# GPSsd1_1.net
KiCad netlist of a schematic drawn in EAGLE
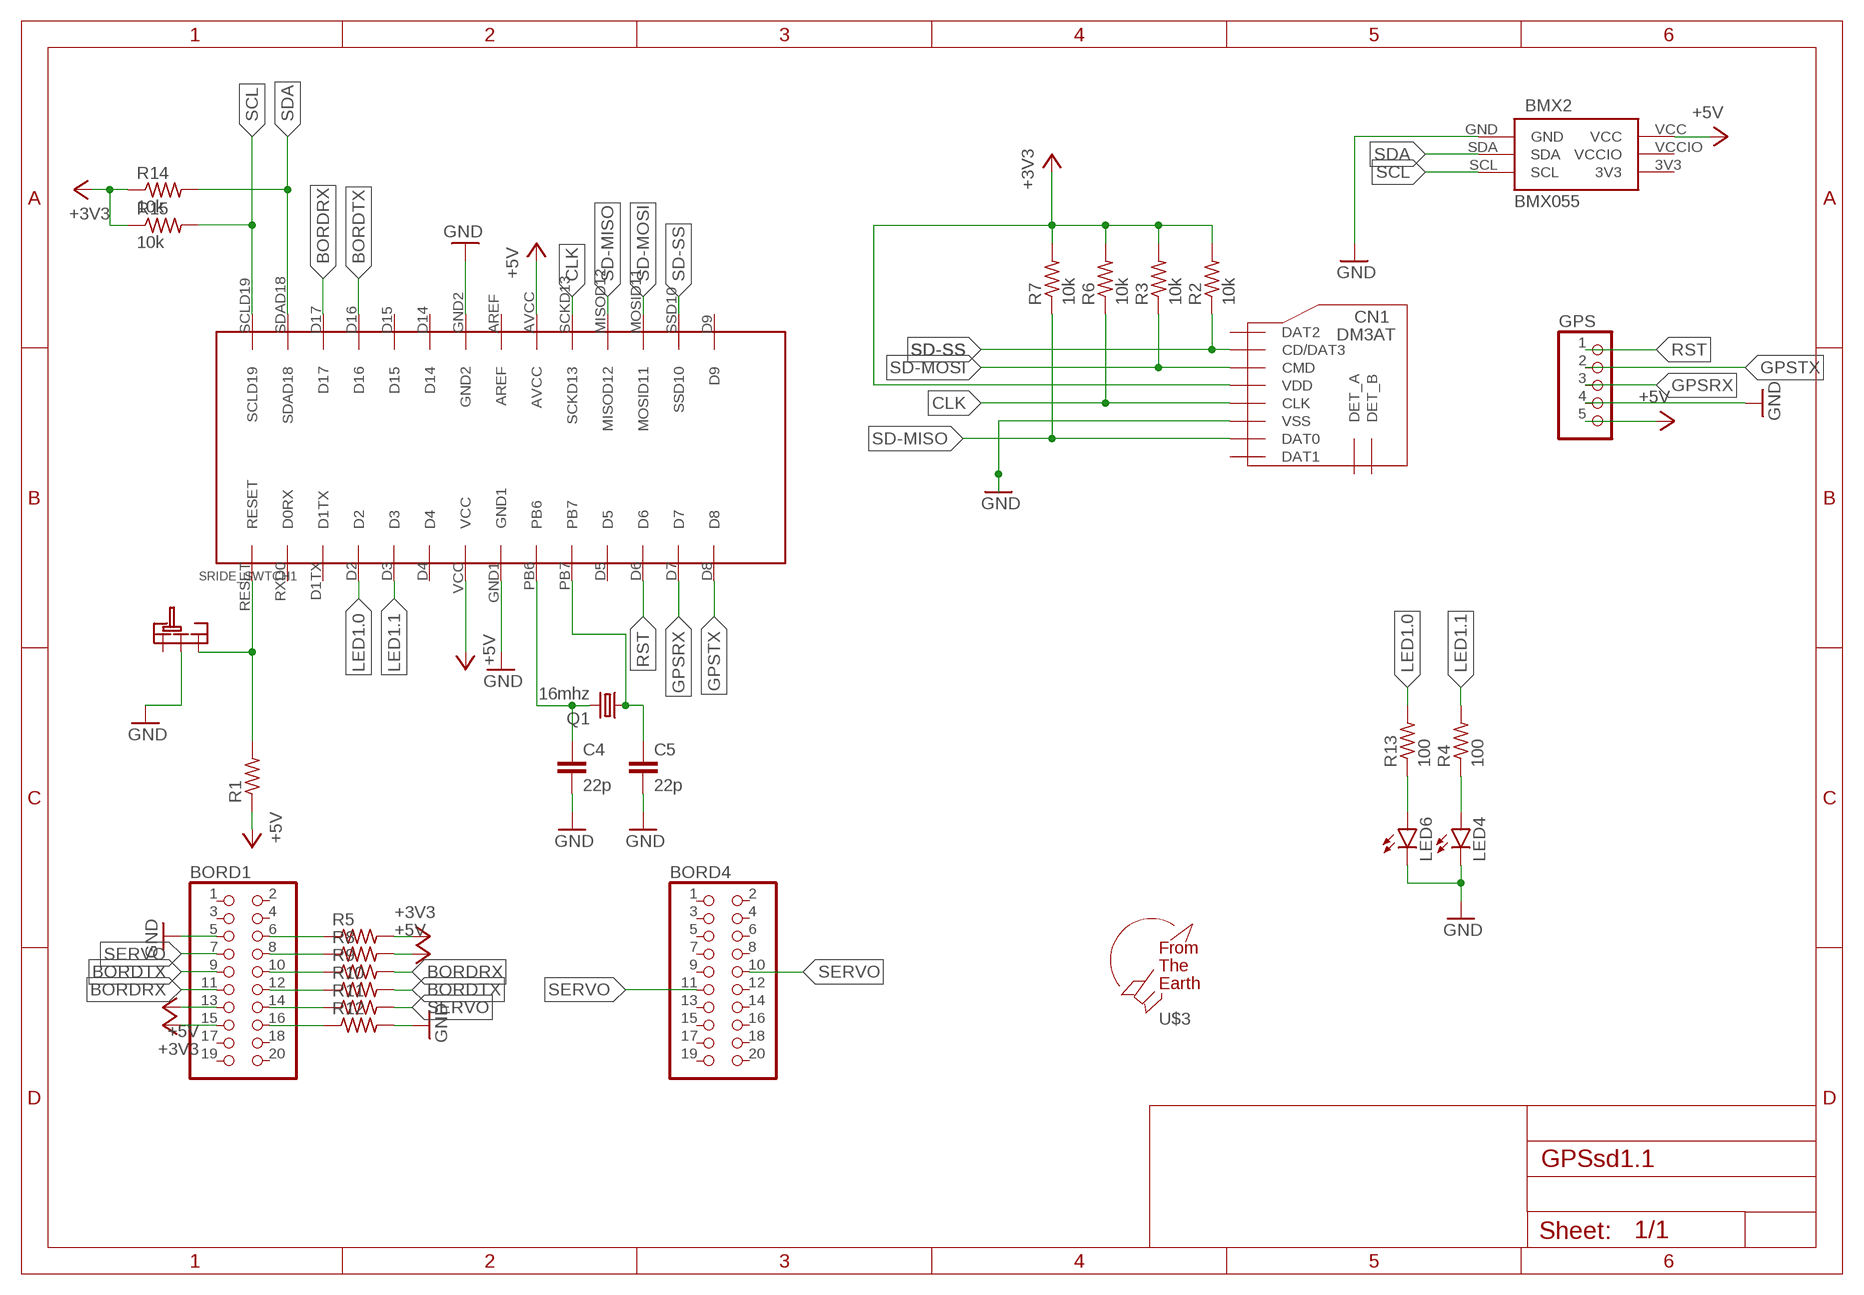
[diagram p0: schematic, sheet 1]

(export (version "E")
  (design (tool "Eeschema 10.0.6"))
  (components
    (comp (ref "BMX2")
      (value "BMX055")
      (footprint "eagle-import:BMX055")
      (libsource (lib "eagle-import") (part "BMX055"))
    )
    (comp (ref "BORD1")
      (value "PINHD-2X10/90")
      (footprint "eagle-import:2X10_90")
      (libsource (lib "eagle-import") (part "PINHD-2X10/90"))
    )
    (comp (ref "BORD4")
      (value "PINHD-2X10/90")
      (footprint "eagle-import:2X10_90")
      (libsource (lib "eagle-import") (part "PINHD-2X10/90"))
    )
    (comp (ref "C4")
      (value "22p")
      (footprint "eagle-import:C025-024X044")
      (libsource (lib "eagle-import") (part "C-EU025-024X044"))
    )
    (comp (ref "C5")
      (value "22p")
      (footprint "eagle-import:C025-024X044")
      (libsource (lib "eagle-import") (part "C-EU025-024X044"))
    )
    (comp (ref "CN1")
      (value "DM3AT")
      (footprint "eagle-import:DM3AT")
      (libsource (lib "eagle-import") (part "DM3AT"))
    )
    (comp (ref "GPS")
      (value "PINHD-1X55X2MM")
      (footprint "eagle-import:1_05X2MM")
      (libsource (lib "eagle-import") (part "PINHD-1X55X2MM"))
    )
    (comp (ref "LED4")
      (value "LED5MM")
      (footprint "eagle-import:LED5MM")
      (libsource (lib "eagle-import") (part "LED5MM"))
    )
    (comp (ref "LED6")
      (value "LED5MM")
      (footprint "eagle-import:LED5MM")
      (libsource (lib "eagle-import") (part "LED5MM"))
    )
    (comp (ref "Q1")
      (value "16mhz")
      (footprint "eagle-import:HC49_S")
      (libsource (lib "eagle-import") (part "CRYSTALHC49S"))
    )
    (comp (ref "R1")
      (value "R-US_0204/7")
      (footprint "eagle-import:0204_7")
      (libsource (lib "eagle-import") (part "R-US_0204/7"))
    )
    (comp (ref "R2")
      (value "10k")
      (footprint "eagle-import:0204_7")
      (libsource (lib "eagle-import") (part "R-US_0204/7"))
    )
    (comp (ref "R3")
      (value "10k")
      (footprint "eagle-import:0204_7")
      (libsource (lib "eagle-import") (part "R-US_0204/7"))
    )
    (comp (ref "R4")
      (value "100")
      (footprint "eagle-import:0204_7")
      (libsource (lib "eagle-import") (part "R-US_0204/7"))
    )
    (comp (ref "R5")
      (value "R-US_0204/7")
      (footprint "eagle-import:0204_7")
      (libsource (lib "eagle-import") (part "R-US_0204/7"))
    )
    (comp (ref "R6")
      (value "10k")
      (footprint "eagle-import:0204_7")
      (libsource (lib "eagle-import") (part "R-US_0204/7"))
    )
    (comp (ref "R7")
      (value "10k")
      (footprint "eagle-import:0204_7")
      (libsource (lib "eagle-import") (part "R-US_0204/7"))
    )
    (comp (ref "R8")
      (value "R-US_0204/7")
      (footprint "eagle-import:0204_7")
      (libsource (lib "eagle-import") (part "R-US_0204/7"))
    )
    (comp (ref "R9")
      (value "R-US_0204/7")
      (footprint "eagle-import:0204_7")
      (libsource (lib "eagle-import") (part "R-US_0204/7"))
    )
    (comp (ref "R10")
      (value "R-US_0204/7")
      (footprint "eagle-import:0204_7")
      (libsource (lib "eagle-import") (part "R-US_0204/7"))
    )
    (comp (ref "R11")
      (value "R-US_0204/7")
      (footprint "eagle-import:0204_7")
      (libsource (lib "eagle-import") (part "R-US_0204/7"))
    )
    (comp (ref "R12")
      (value "R-US_0204/7")
      (footprint "eagle-import:0204_7")
      (libsource (lib "eagle-import") (part "R-US_0204/7"))
    )
    (comp (ref "R13")
      (value "100")
      (footprint "eagle-import:0204_7")
      (libsource (lib "eagle-import") (part "R-US_0204/7"))
    )
    (comp (ref "R14")
      (value "10k")
      (footprint "eagle-import:0204_7")
      (libsource (lib "eagle-import") (part "R-US_0204/7"))
    )
    (comp (ref "R15")
      (value "10k")
      (footprint "eagle-import:0204_7")
      (libsource (lib "eagle-import") (part "R-US_0204/7"))
    )
    (comp (ref "SRIDE_SWTCH1")
      (value "SRIDE_SWITCH")
      (footprint "eagle-import:SRIDE_SWITCH")
      (libsource (lib "eagle-import") (part "SRIDE_SWITCH"))
    )
    (comp (ref "U$1")
      (value "ATMEGA238P")
      (footprint "eagle-import:ATMEGA328P")
      (libsource (lib "eagle-import") (part "ATMEGA238P"))
    )
    (comp (ref "U$3")
      (value "F.T.E.LOGO")
      (footprint "eagle-import:LOGO")
      (libsource (lib "eagle-import") (part "F.T.E.LOGO"))
    )
  )
  (nets
    (net (code "1") (name "+3V3") (class "Default")
      (node (ref "BORD1") (pin "15") (pinfunction "15_15") (pintype "passive"))
      (node (ref "CN1") (pin "VDD") (pinfunction "VDD_VDD") (pintype "bidirectional"))
      (node (ref "R14") (pin "1") (pinfunction "1_1") (pintype "passive"))
      (node (ref "R15") (pin "1") (pinfunction "1_1") (pintype "passive"))
      (node (ref "R2") (pin "2") (pinfunction "2_2") (pintype "passive"))
      (node (ref "R3") (pin "2") (pinfunction "2_2") (pintype "passive"))
      (node (ref "R5") (pin "2") (pinfunction "2_2") (pintype "passive"))
      (node (ref "R6") (pin "2") (pinfunction "2_2") (pintype "passive"))
      (node (ref "R7") (pin "2") (pinfunction "2_2") (pintype "passive"))
    )
    (net (code "2") (name "+5V") (class "Default")
      (node (ref "BMX2") (pin "VCC") (pinfunction "VCC_VCC") (pintype "power_in"))
      (node (ref "BORD1") (pin "13") (pinfunction "13_13") (pintype "passive"))
      (node (ref "GPS") (pin "5") (pinfunction "5_5") (pintype "passive"))
      (node (ref "R1") (pin "1") (pinfunction "1_1") (pintype "passive"))
      (node (ref "R8") (pin "2") (pinfunction "2_2") (pintype "passive"))
      (node (ref "U$1") (pin "AVCC") (pinfunction "AVCC_AVCC") (pintype "bidirectional"))
      (node (ref "U$1") (pin "VCC") (pinfunction "VCC_VCC") (pintype "bidirectional"))
    )
    (net (code "3") (name "/3V3") (class "Default")
      (node (ref "BMX2") (pin "3V3") (pinfunction "3V3_3V3") (pintype "power_in"))
    )
    (net (code "4") (name "/VCCIO") (class "Default")
      (node (ref "BMX2") (pin "VCCIO") (pinfunction "VCCIO_VCCIO") (pintype "power_in"))
    )
    (net (code "5") (name "BORDRX") (class "Default")
      (node (ref "BORD1") (pin "11") (pinfunction "11_11") (pintype "passive"))
      (node (ref "R9") (pin "2") (pinfunction "2_2") (pintype "passive"))
      (node (ref "U$1") (pin "D17") (pinfunction "D17_D17") (pintype "bidirectional"))
    )
    (net (code "6") (name "BORDTX") (class "Default")
      (node (ref "BORD1") (pin "9") (pinfunction "9_9") (pintype "passive"))
      (node (ref "R10") (pin "2") (pinfunction "2_2") (pintype "passive"))
      (node (ref "U$1") (pin "D16") (pinfunction "D16_D16") (pintype "bidirectional"))
    )
    (net (code "7") (name "CLK") (class "Default")
      (node (ref "CN1") (pin "CLK") (pinfunction "CLK_CLK") (pintype "bidirectional"))
      (node (ref "R6") (pin "1") (pinfunction "1_1") (pintype "passive"))
      (node (ref "U$1") (pin "SCKD13") (pinfunction "SCKD13_SCKD13") (pintype "bidirectional"))
    )
    (net (code "8") (name "GND") (class "Default")
      (node (ref "BMX2") (pin "GND") (pinfunction "GND_GND") (pintype "power_in"))
      (node (ref "BORD1") (pin "5") (pinfunction "5_5") (pintype "passive"))
      (node (ref "C4") (pin "2") (pinfunction "2_2") (pintype "passive"))
      (node (ref "C5") (pin "2") (pinfunction "2_2") (pintype "passive"))
      (node (ref "CN1") (pin "VSS") (pinfunction "VSS_VSS") (pintype "bidirectional"))
      (node (ref "GPS") (pin "4") (pinfunction "4_4") (pintype "passive"))
      (node (ref "LED4") (pin "K") (pinfunction "C_K") (pintype "passive"))
      (node (ref "LED6") (pin "K") (pinfunction "C_K") (pintype "passive"))
      (node (ref "R12") (pin "2") (pinfunction "2_2") (pintype "passive"))
      (node (ref "SRIDE_SWTCH1") (pin "LR") (pinfunction "LR_LR") (pintype "bidirectional"))
      (node (ref "U$1") (pin "GND1") (pinfunction "GND1_GND1") (pintype "bidirectional"))
      (node (ref "U$1") (pin "GND2") (pinfunction "GND2_GND2") (pintype "bidirectional"))
    )
    (net (code "9") (name "GPSRX") (class "Default")
      (node (ref "GPS") (pin "3") (pinfunction "3_3") (pintype "passive"))
      (node (ref "U$1") (pin "D7") (pinfunction "D7_D7") (pintype "bidirectional"))
    )
    (net (code "10") (name "GPSTX") (class "Default")
      (node (ref "GPS") (pin "2") (pinfunction "2_2") (pintype "passive"))
      (node (ref "U$1") (pin "D8") (pinfunction "D8_D8") (pintype "bidirectional"))
    )
    (net (code "11") (name "LED1.0") (class "Default")
      (node (ref "R13") (pin "2") (pinfunction "2_2") (pintype "passive"))
      (node (ref "U$1") (pin "D2") (pinfunction "D2_D2") (pintype "bidirectional"))
    )
    (net (code "12") (name "LED1.1") (class "Default")
      (node (ref "R4") (pin "2") (pinfunction "2_2") (pintype "passive"))
      (node (ref "U$1") (pin "D3") (pinfunction "D3_D3") (pintype "bidirectional"))
    )
    (net (code "13") (name "Net-(BORD1-Pad6)") (class "Default")
      (node (ref "BORD1") (pin "6") (pinfunction "6_6") (pintype "passive"))
      (node (ref "R5") (pin "1") (pinfunction "1_1") (pintype "passive"))
    )
    (net (code "14") (name "Net-(BORD1-Pad8)") (class "Default")
      (node (ref "BORD1") (pin "8") (pinfunction "8_8") (pintype "passive"))
      (node (ref "R8") (pin "1") (pinfunction "1_1") (pintype "passive"))
    )
    (net (code "15") (name "Net-(BORD1-Pad10)") (class "Default")
      (node (ref "BORD1") (pin "10") (pinfunction "10_10") (pintype "passive"))
      (node (ref "R9") (pin "1") (pinfunction "1_1") (pintype "passive"))
    )
    (net (code "16") (name "Net-(BORD1-Pad12)") (class "Default")
      (node (ref "BORD1") (pin "12") (pinfunction "12_12") (pintype "passive"))
      (node (ref "R10") (pin "1") (pinfunction "1_1") (pintype "passive"))
    )
    (net (code "17") (name "Net-(BORD1-Pad14)") (class "Default")
      (node (ref "BORD1") (pin "14") (pinfunction "14_14") (pintype "passive"))
      (node (ref "R11") (pin "1") (pinfunction "1_1") (pintype "passive"))
    )
    (net (code "18") (name "Net-(BORD1-Pad16)") (class "Default")
      (node (ref "BORD1") (pin "16") (pinfunction "16_16") (pintype "passive"))
      (node (ref "R12") (pin "1") (pinfunction "1_1") (pintype "passive"))
    )
    (net (code "19") (name "Net-(C4-Pad1)") (class "Default")
      (node (ref "C4") (pin "1") (pinfunction "1_1") (pintype "passive"))
      (node (ref "Q1") (pin "2") (pinfunction "2_2") (pintype "passive"))
      (node (ref "U$1") (pin "PB6") (pinfunction "PB6_PB6") (pintype "bidirectional"))
    )
    (net (code "20") (name "Net-(C5-Pad1)") (class "Default")
      (node (ref "C5") (pin "1") (pinfunction "1_1") (pintype "passive"))
      (node (ref "Q1") (pin "1") (pinfunction "1_1") (pintype "passive"))
      (node (ref "U$1") (pin "PB7") (pinfunction "PB7_PB7") (pintype "bidirectional"))
    )
    (net (code "21") (name "Net-(LED4-PadA)") (class "Default")
      (node (ref "LED4") (pin "A") (pinfunction "A_A") (pintype "passive"))
      (node (ref "R4") (pin "1") (pinfunction "1_1") (pintype "passive"))
    )
    (net (code "22") (name "Net-(LED6-PadA)") (class "Default")
      (node (ref "LED6") (pin "A") (pinfunction "A_A") (pintype "passive"))
      (node (ref "R13") (pin "1") (pinfunction "1_1") (pintype "passive"))
    )
    (net (code "23") (name "Net-(R1-Pad2)") (class "Default")
      (node (ref "R1") (pin "2") (pinfunction "2_2") (pintype "passive"))
      (node (ref "SRIDE_SWTCH1") (pin "R") (pinfunction "R_R") (pintype "bidirectional"))
      (node (ref "U$1") (pin "RESET") (pinfunction "RESET_RESET") (pintype "bidirectional"))
    )
    (net (code "24") (name "RST") (class "Default")
      (node (ref "GPS") (pin "1") (pinfunction "1_1") (pintype "passive"))
      (node (ref "U$1") (pin "D6") (pinfunction "D6_D6") (pintype "bidirectional"))
    )
    (net (code "25") (name "SCL") (class "Default")
      (node (ref "BMX2") (pin "SCL") (pinfunction "SCL_SCL") (pintype "bidirectional"))
      (node (ref "R15") (pin "2") (pinfunction "2_2") (pintype "passive"))
      (node (ref "U$1") (pin "SCLD19") (pinfunction "SCLD19_SCLD19") (pintype "bidirectional"))
    )
    (net (code "26") (name "SD-MISO") (class "Default")
      (node (ref "CN1") (pin "DAT0") (pinfunction "DAT0_DAT0") (pintype "bidirectional"))
      (node (ref "R7") (pin "1") (pinfunction "1_1") (pintype "passive"))
      (node (ref "U$1") (pin "MISOD12") (pinfunction "MISOD12_MISOD12") (pintype "bidirectional"))
    )
    (net (code "27") (name "SD-MOSI") (class "Default")
      (node (ref "CN1") (pin "CMD") (pinfunction "CMD_CMD") (pintype "bidirectional"))
      (node (ref "R3") (pin "1") (pinfunction "1_1") (pintype "passive"))
      (node (ref "U$1") (pin "MOSID11") (pinfunction "MOSID11_MOSID11") (pintype "bidirectional"))
    )
    (net (code "28") (name "SD-SS") (class "Default")
      (node (ref "CN1") (pin "CD/DAT3") (pinfunction "CD/DAT3_CD/DAT3") (pintype "bidirectional"))
      (node (ref "R2") (pin "1") (pinfunction "1_1") (pintype "passive"))
      (node (ref "U$1") (pin "SSD10") (pinfunction "SSD10_SSD10") (pintype "bidirectional"))
    )
    (net (code "29") (name "SDA") (class "Default")
      (node (ref "BMX2") (pin "SDA") (pinfunction "SDA_SDA") (pintype "bidirectional"))
      (node (ref "R14") (pin "2") (pinfunction "2_2") (pintype "passive"))
      (node (ref "U$1") (pin "SDAD18") (pinfunction "SDAD18_SDAD18") (pintype "bidirectional"))
    )
    (net (code "30") (name "SERVO") (class "Default")
      (node (ref "BORD1") (pin "7") (pinfunction "7_7") (pintype "passive"))
      (node (ref "BORD4") (pin "10") (pinfunction "10_10") (pintype "passive"))
      (node (ref "BORD4") (pin "11") (pinfunction "11_11") (pintype "passive"))
      (node (ref "R11") (pin "2") (pinfunction "2_2") (pintype "passive"))
    )
    (net (code "31") (name "unconnected-(BORD1-Pad1)") (class "Default")
      (node (ref "BORD1") (pin "1") (pinfunction "1_1") (pintype "passive"))
    )
    (net (code "32") (name "unconnected-(BORD1-Pad2)") (class "Default")
      (node (ref "BORD1") (pin "2") (pinfunction "2_2") (pintype "passive"))
    )
    (net (code "33") (name "unconnected-(BORD1-Pad3)") (class "Default")
      (node (ref "BORD1") (pin "3") (pinfunction "3_3") (pintype "passive"))
    )
    (net (code "34") (name "unconnected-(BORD1-Pad4)") (class "Default")
      (node (ref "BORD1") (pin "4") (pinfunction "4_4") (pintype "passive"))
    )
    (net (code "35") (name "unconnected-(BORD1-Pad17)") (class "Default")
      (node (ref "BORD1") (pin "17") (pinfunction "17_17") (pintype "passive"))
    )
    (net (code "36") (name "unconnected-(BORD1-Pad18)") (class "Default")
      (node (ref "BORD1") (pin "18") (pinfunction "18_18") (pintype "passive"))
    )
    (net (code "37") (name "unconnected-(BORD1-Pad19)") (class "Default")
      (node (ref "BORD1") (pin "19") (pinfunction "19_19") (pintype "passive"))
    )
    (net (code "38") (name "unconnected-(BORD1-Pad20)") (class "Default")
      (node (ref "BORD1") (pin "20") (pinfunction "20_20") (pintype "passive"))
    )
    (net (code "39") (name "unconnected-(BORD4-Pad1)") (class "Default")
      (node (ref "BORD4") (pin "1") (pinfunction "1_1") (pintype "passive"))
    )
    (net (code "40") (name "unconnected-(BORD4-Pad2)") (class "Default")
      (node (ref "BORD4") (pin "2") (pinfunction "2_2") (pintype "passive"))
    )
    (net (code "41") (name "unconnected-(BORD4-Pad3)") (class "Default")
      (node (ref "BORD4") (pin "3") (pinfunction "3_3") (pintype "passive"))
    )
    (net (code "42") (name "unconnected-(BORD4-Pad4)") (class "Default")
      (node (ref "BORD4") (pin "4") (pinfunction "4_4") (pintype "passive"))
    )
    (net (code "43") (name "unconnected-(BORD4-Pad5)") (class "Default")
      (node (ref "BORD4") (pin "5") (pinfunction "5_5") (pintype "passive"))
    )
    (net (code "44") (name "unconnected-(BORD4-Pad6)") (class "Default")
      (node (ref "BORD4") (pin "6") (pinfunction "6_6") (pintype "passive"))
    )
    (net (code "45") (name "unconnected-(BORD4-Pad7)") (class "Default")
      (node (ref "BORD4") (pin "7") (pinfunction "7_7") (pintype "passive"))
    )
    (net (code "46") (name "unconnected-(BORD4-Pad8)") (class "Default")
      (node (ref "BORD4") (pin "8") (pinfunction "8_8") (pintype "passive"))
    )
    (net (code "47") (name "unconnected-(BORD4-Pad9)") (class "Default")
      (node (ref "BORD4") (pin "9") (pinfunction "9_9") (pintype "passive"))
    )
    (net (code "48") (name "unconnected-(BORD4-Pad12)") (class "Default")
      (node (ref "BORD4") (pin "12") (pinfunction "12_12") (pintype "passive"))
    )
    (net (code "49") (name "unconnected-(BORD4-Pad13)") (class "Default")
      (node (ref "BORD4") (pin "13") (pinfunction "13_13") (pintype "passive"))
    )
    (net (code "50") (name "unconnected-(BORD4-Pad14)") (class "Default")
      (node (ref "BORD4") (pin "14") (pinfunction "14_14") (pintype "passive"))
    )
    (net (code "51") (name "unconnected-(BORD4-Pad15)") (class "Default")
      (node (ref "BORD4") (pin "15") (pinfunction "15_15") (pintype "passive"))
    )
    (net (code "52") (name "unconnected-(BORD4-Pad16)") (class "Default")
      (node (ref "BORD4") (pin "16") (pinfunction "16_16") (pintype "passive"))
    )
    (net (code "53") (name "unconnected-(BORD4-Pad17)") (class "Default")
      (node (ref "BORD4") (pin "17") (pinfunction "17_17") (pintype "passive"))
    )
    (net (code "54") (name "unconnected-(BORD4-Pad18)") (class "Default")
      (node (ref "BORD4") (pin "18") (pinfunction "18_18") (pintype "passive"))
    )
    (net (code "55") (name "unconnected-(BORD4-Pad19)") (class "Default")
      (node (ref "BORD4") (pin "19") (pinfunction "19_19") (pintype "passive"))
    )
    (net (code "56") (name "unconnected-(BORD4-Pad20)") (class "Default")
      (node (ref "BORD4") (pin "20") (pinfunction "20_20") (pintype "passive"))
    )
    (net (code "57") (name "unconnected-(CN1-PadDAT1)") (class "Default")
      (node (ref "CN1") (pin "DAT1") (pinfunction "DAT1_DAT1") (pintype "bidirectional"))
    )
    (net (code "58") (name "unconnected-(CN1-PadDAT2)") (class "Default")
      (node (ref "CN1") (pin "DAT2") (pinfunction "DAT2_DAT2") (pintype "bidirectional"))
    )
    (net (code "59") (name "unconnected-(CN1-PadDET_A)") (class "Default")
      (node (ref "CN1") (pin "DET_A") (pinfunction "DET_A_DET_A") (pintype "bidirectional"))
    )
    (net (code "60") (name "unconnected-(CN1-PadDET_B)") (class "Default")
      (node (ref "CN1") (pin "DET_B") (pinfunction "DET_B_DET_B") (pintype "bidirectional"))
    )
    (net (code "61") (name "unconnected-(SRIDE_SWTCH1-PadL)") (class "Default")
      (node (ref "SRIDE_SWTCH1") (pin "L") (pinfunction "L_L") (pintype "bidirectional"))
    )
    (net (code "62") (name "unconnected-(U$1-D0RX-PadRXD0)") (class "Default")
      (node (ref "U$1") (pin "RXD0") (pinfunction "D0RX_RXD0") (pintype "bidirectional"))
    )
    (net (code "63") (name "unconnected-(U$1-PadAREF)") (class "Default")
      (node (ref "U$1") (pin "AREF") (pinfunction "AREF_AREF") (pintype "bidirectional"))
    )
    (net (code "64") (name "unconnected-(U$1-PadD1TX)") (class "Default")
      (node (ref "U$1") (pin "D1TX") (pinfunction "D1TX_D1TX") (pintype "bidirectional"))
    )
    (net (code "65") (name "unconnected-(U$1-PadD4)") (class "Default")
      (node (ref "U$1") (pin "D4") (pinfunction "D4_D4") (pintype "bidirectional"))
    )
    (net (code "66") (name "unconnected-(U$1-PadD5)") (class "Default")
      (node (ref "U$1") (pin "D5") (pinfunction "D5_D5") (pintype "bidirectional"))
    )
    (net (code "67") (name "unconnected-(U$1-PadD9)") (class "Default")
      (node (ref "U$1") (pin "D9") (pinfunction "D9_D9") (pintype "bidirectional"))
    )
    (net (code "68") (name "unconnected-(U$1-PadD14)") (class "Default")
      (node (ref "U$1") (pin "D14") (pinfunction "D14_D14") (pintype "bidirectional"))
    )
    (net (code "69") (name "unconnected-(U$1-PadD15)") (class "Default")
      (node (ref "U$1") (pin "D15") (pinfunction "D15_D15") (pintype "bidirectional"))
    )
  )
)
